# loicpinuela2.net
KiCad netlist of a schematic drawn in Altium Designer
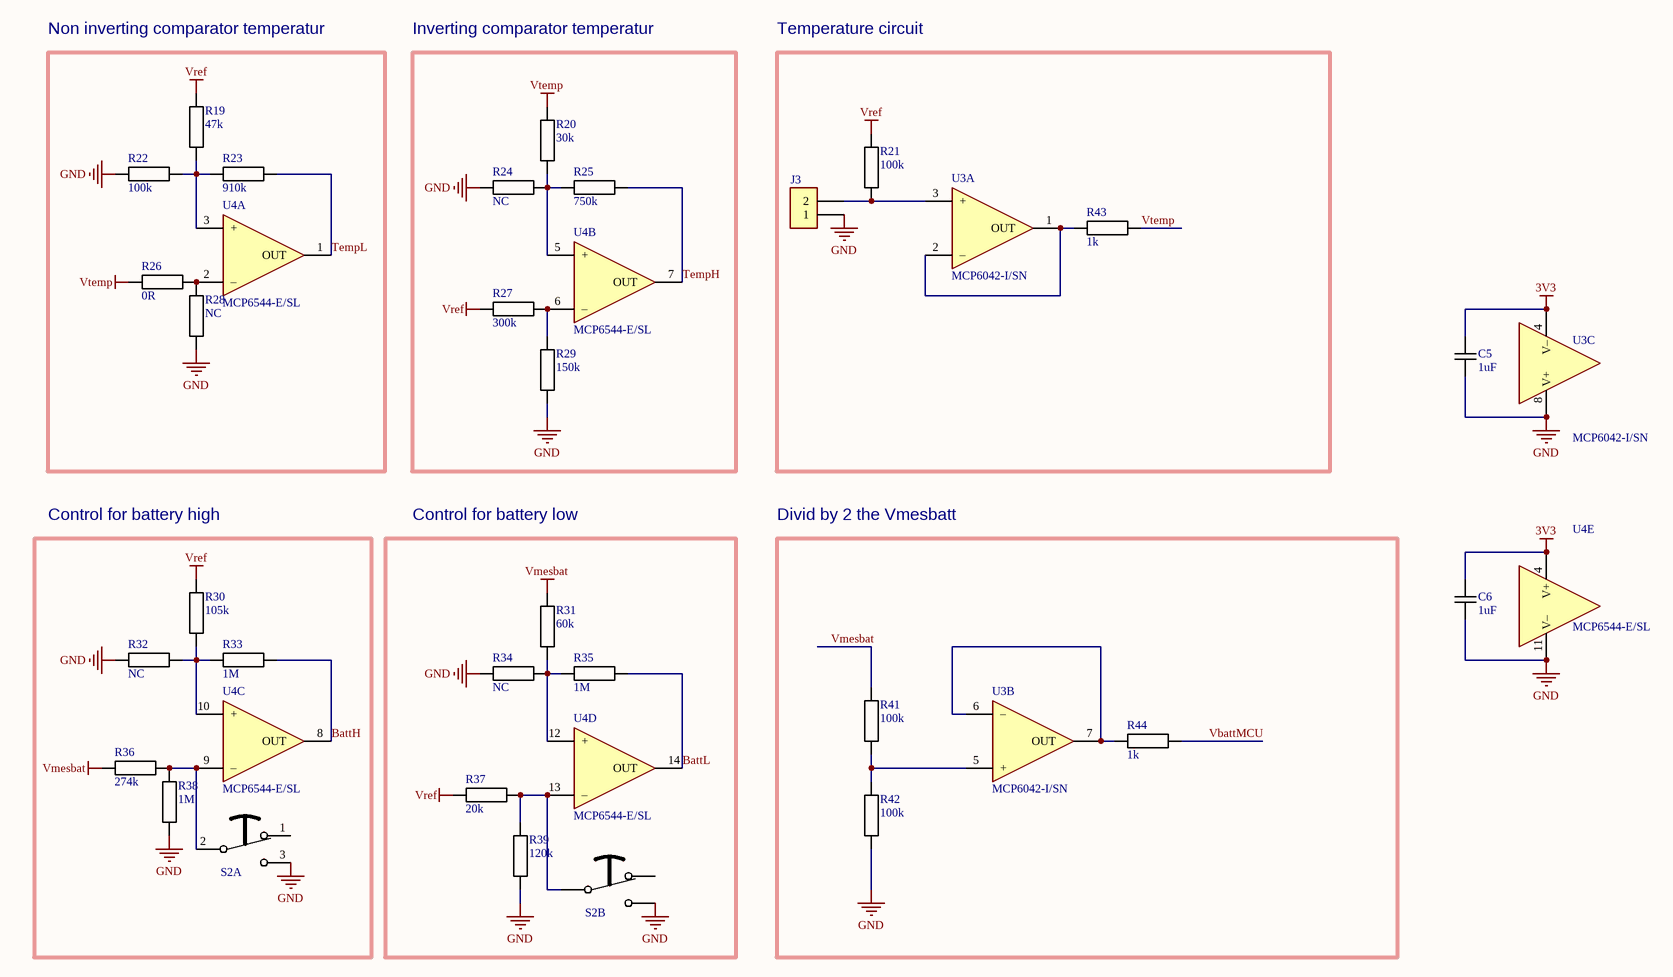
[diagram p0: loicpinuela2.SchDoc]

(export (version "E")
  (design (tool "Eeschema 10.0.6"))
  (components
    (comp (ref "C5")
      (value "1uF")
      (footprint "CAPACITOR 2012 REFLOW")
      (description "Capacitor")
      (libsource (lib "Capacitor") (part "Capacitor"))
    )
    (comp (ref "C6")
      (value "1uF")
      (footprint "CAPACITOR 2012 REFLOW")
      (description "Capacitor")
      (libsource (lib "Capacitor") (part "Capacitor"))
    )
    (comp (ref "J3")
      (value "~")
      (footprint "Socket1x2 P2.54")
      (description "Receptacle connector")
      (libsource (lib "PinHeader") (part "Socket1x2"))
    )
    (comp (ref "R19")
      (value "47k")
      (footprint "RESISTOR 2012 REFLOW")
      (description "Resistor")
      (fields (field (name "TOLERANCE") "1%"))
      (libsource (lib "Resistor") (part "Resistor"))
    )
    (comp (ref "R20")
      (value "30k")
      (footprint "RESISTOR 2012 REFLOW")
      (description "Resistor")
      (fields (field (name "TOLERANCE") "1%"))
      (libsource (lib "Resistor") (part "Resistor"))
    )
    (comp (ref "R21")
      (value "100k")
      (footprint "RESISTOR 2012 REFLOW")
      (description "Resistor")
      (fields (field (name "TOLERANCE") "1%"))
      (libsource (lib "Resistor") (part "Resistor"))
    )
    (comp (ref "R22")
      (value "100k")
      (footprint "RESISTOR 2012 REFLOW")
      (description "Resistor")
      (fields (field (name "TOLERANCE") "1%"))
      (libsource (lib "Resistor") (part "Resistor"))
    )
    (comp (ref "R23")
      (value "910k")
      (footprint "RESISTOR 2012 REFLOW")
      (description "Resistor")
      (fields (field (name "TOLERANCE") "1%"))
      (libsource (lib "Resistor") (part "Resistor"))
    )
    (comp (ref "R24")
      (value "NC")
      (footprint "RESISTOR 2012 REFLOW")
      (description "Resistor")
      (fields (field (name "TOLERANCE") "1%"))
      (libsource (lib "Resistor") (part "Resistor"))
    )
    (comp (ref "R25")
      (value "750k")
      (footprint "RESISTOR 2012 REFLOW")
      (description "Resistor")
      (fields (field (name "TOLERANCE") "1%"))
      (libsource (lib "Resistor") (part "Resistor"))
    )
    (comp (ref "R26")
      (value "0R")
      (footprint "RESISTOR 2012 REFLOW")
      (description "Resistor")
      (fields (field (name "TOLERANCE") "1%"))
      (libsource (lib "Resistor") (part "Resistor"))
    )
    (comp (ref "R27")
      (value "300k")
      (footprint "RESISTOR 2012 REFLOW")
      (description "Resistor")
      (fields (field (name "TOLERANCE") "1%"))
      (libsource (lib "Resistor") (part "Resistor"))
    )
    (comp (ref "R28")
      (value "NC")
      (footprint "RESISTOR 2012 REFLOW")
      (description "Resistor")
      (fields (field (name "TOLERANCE") "1%"))
      (libsource (lib "Resistor") (part "Resistor"))
    )
    (comp (ref "R29")
      (value "150k")
      (footprint "RESISTOR 2012 REFLOW")
      (description "Resistor")
      (fields (field (name "TOLERANCE") "1%"))
      (libsource (lib "Resistor") (part "Resistor"))
    )
    (comp (ref "R30")
      (value "105k")
      (footprint "RESISTOR 2012 REFLOW")
      (description "Resistor")
      (fields (field (name "TOLERANCE") "1%"))
      (libsource (lib "Resistor") (part "Resistor"))
    )
    (comp (ref "R31")
      (value "60k")
      (footprint "RESISTOR 2012 REFLOW")
      (description "Resistor")
      (fields (field (name "TOLERANCE") "1%"))
      (libsource (lib "Resistor") (part "Resistor"))
    )
    (comp (ref "R32")
      (value "NC")
      (footprint "RESISTOR 2012 REFLOW")
      (description "Resistor")
      (fields (field (name "TOLERANCE") "1%"))
      (libsource (lib "Resistor") (part "Resistor"))
    )
    (comp (ref "R33")
      (value "1M")
      (footprint "RESISTOR 2012 REFLOW")
      (description "Resistor")
      (fields (field (name "TOLERANCE") "1%"))
      (libsource (lib "Resistor") (part "Resistor"))
    )
    (comp (ref "R34")
      (value "NC")
      (footprint "RESISTOR 2012 REFLOW")
      (description "Resistor")
      (fields (field (name "TOLERANCE") "1%"))
      (libsource (lib "Resistor") (part "Resistor"))
    )
    (comp (ref "R35")
      (value "1M")
      (footprint "RESISTOR 2012 REFLOW")
      (description "Resistor")
      (fields (field (name "TOLERANCE") "1%"))
      (libsource (lib "Resistor") (part "Resistor"))
    )
    (comp (ref "R36")
      (value "274k")
      (footprint "RESISTOR 2012 REFLOW")
      (description "Resistor")
      (fields (field (name "TOLERANCE") "1%"))
      (libsource (lib "Resistor") (part "Resistor"))
    )
    (comp (ref "R37")
      (value "20k")
      (footprint "RESISTOR 2012 REFLOW")
      (description "Resistor")
      (fields (field (name "TOLERANCE") "1%"))
      (libsource (lib "Resistor") (part "Resistor"))
    )
    (comp (ref "R38")
      (value "1M")
      (footprint "RESISTOR 2012 REFLOW")
      (description "Resistor")
      (fields (field (name "TOLERANCE") "1%"))
      (libsource (lib "Resistor") (part "Resistor"))
    )
    (comp (ref "R39")
      (value "120k")
      (footprint "RESISTOR 2012 REFLOW")
      (description "Resistor")
      (fields (field (name "TOLERANCE") "1%"))
      (libsource (lib "Resistor") (part "Resistor"))
    )
    (comp (ref "R41")
      (value "100k")
      (footprint "RESISTOR 2012 REFLOW")
      (description "Resistor")
      (fields (field (name "TOLERANCE") "1%"))
      (libsource (lib "Resistor") (part "Resistor"))
    )
    (comp (ref "R42")
      (value "100k")
      (footprint "RESISTOR 2012 REFLOW")
      (description "Resistor")
      (fields (field (name "TOLERANCE") "1%"))
      (libsource (lib "Resistor") (part "Resistor"))
    )
    (comp (ref "R43")
      (value "1k")
      (footprint "RESISTOR 2012 REFLOW")
      (description "Resistor")
      (fields (field (name "TOLERANCE") "1%"))
      (libsource (lib "Resistor") (part "Resistor"))
    )
    (comp (ref "R44")
      (value "1k")
      (footprint "RESISTOR 2012 REFLOW")
      (description "Resistor")
      (fields (field (name "TOLERANCE") "1%"))
      (libsource (lib "Resistor") (part "Resistor"))
    )
    (comp (ref "S2")
      (value "*")
      (footprint "Push Button E-Switch TL2233")
      (description "Pushbutton, DPDT, SMD Switch")
      (libsource (lib "Button") (part "Push Button E-Switch TL2233"))
    )
    (comp (ref "U3")
      (value "MCP6042-I/SN")
      (footprint "SO8 P1.27 C4.0X5.0 H1.75")
      (description "Generic dual OPA 8 pins")
      (libsource (lib "Amplifier") (part "OPA DUAL"))
    )
    (comp (ref "U4")
      (value "MCP6544-E/SL")
      (footprint "SO14 P1.27 C4.0X8.8 H1.75")
      (description "Generic quad comparator 14 pins, Outpout PIN 1-7-18-14")
      (libsource (lib "Comparator") (part "COMPARATOR QUAD OUT PIN 1-7-8-14"))
    )
  )
  (nets
    (net (code "1") (name "/BattH") (class "Default")
      (node (ref "R33") (pin "2") (pinfunction "2_2") (pintype "passive"))
      (node (ref "U4") (pin "8") (pinfunction "OUT_8") (pintype "passive"))
    )
    (net (code "2") (name "/BattL") (class "Default")
      (node (ref "R35") (pin "2") (pinfunction "2_2") (pintype "passive"))
      (node (ref "U4") (pin "14") (pinfunction "OUT_14") (pintype "passive"))
    )
    (net (code "3") (name "/TempH") (class "Default")
      (node (ref "R25") (pin "2") (pinfunction "2_2") (pintype "passive"))
      (node (ref "U4") (pin "7") (pinfunction "OUT_7") (pintype "passive"))
    )
    (net (code "4") (name "/TempL") (class "Default")
      (node (ref "R23") (pin "2") (pinfunction "2_2") (pintype "passive"))
      (node (ref "U4") (pin "1") (pinfunction "OUT_1") (pintype "passive"))
    )
    (net (code "5") (name "/VbattMCU") (class "Default")
      (node (ref "R44") (pin "2") (pinfunction "2_2") (pintype "passive"))
    )
    (net (code "6") (name "3V3") (class "Default")
      (node (ref "C5") (pin "2") (pinfunction "2_2") (pintype "passive"))
      (node (ref "C6") (pin "2") (pinfunction "2_2") (pintype "passive"))
      (node (ref "U3") (pin "4") (pinfunction "V–_4") (pintype "passive"))
      (node (ref "U4") (pin "4") (pinfunction "V+_4") (pintype "passive"))
    )
    (net (code "7") (name "GND") (class "Default")
      (node (ref "C5") (pin "1") (pinfunction "1_1") (pintype "passive"))
      (node (ref "C6") (pin "1") (pinfunction "1_1") (pintype "passive"))
      (node (ref "J3") (pin "1") (pinfunction "1_1") (pintype "passive"))
      (node (ref "R22") (pin "1") (pinfunction "1_1") (pintype "passive"))
      (node (ref "R24") (pin "1") (pinfunction "1_1") (pintype "passive"))
      (node (ref "R28") (pin "1") (pinfunction "1_1") (pintype "passive"))
      (node (ref "R29") (pin "2") (pinfunction "2_2") (pintype "passive"))
      (node (ref "R32") (pin "1") (pinfunction "1_1") (pintype "passive"))
      (node (ref "R34") (pin "1") (pinfunction "1_1") (pintype "passive"))
      (node (ref "R38") (pin "1") (pinfunction "1_1") (pintype "passive"))
      (node (ref "R39") (pin "2") (pinfunction "2_2") (pintype "passive"))
      (node (ref "R42") (pin "1") (pinfunction "1_1") (pintype "passive"))
      (node (ref "S2") (pin "3") (pinfunction "NO1_3") (pintype "passive"))
      (node (ref "S2") (pin "4") (pinfunction "NO2_4") (pintype "passive"))
      (node (ref "U3") (pin "8") (pinfunction "V+_8") (pintype "passive"))
      (node (ref "U4") (pin "11") (pinfunction "V–_11") (pintype "passive"))
    )
    (net (code "8") (name "Net-(S2A-COM1)") (class "Default")
      (node (ref "R36") (pin "2") (pinfunction "2_2") (pintype "passive"))
      (node (ref "R38") (pin "2") (pinfunction "2_2") (pintype "passive"))
      (node (ref "S2") (pin "2") (pinfunction "COM1_2") (pintype "passive"))
      (node (ref "U4") (pin "9") (pinfunction "–_9") (pintype "passive"))
    )
    (net (code "9") (name "Net-(S2B-COM2)") (class "Default")
      (node (ref "R37") (pin "2") (pinfunction "2_2") (pintype "passive"))
      (node (ref "R39") (pin "1") (pinfunction "1_1") (pintype "passive"))
      (node (ref "S2") (pin "5") (pinfunction "COM2_5") (pintype "passive"))
      (node (ref "U4") (pin "13") (pinfunction "–_13") (pintype "passive"))
    )
    (net (code "10") (name "Net-(U3A-+)") (class "Default")
      (node (ref "J3") (pin "2") (pinfunction "2_2") (pintype "passive"))
      (node (ref "R21") (pin "1") (pinfunction "1_1") (pintype "passive"))
      (node (ref "U3") (pin "3") (pinfunction "+_3") (pintype "passive"))
    )
    (net (code "11") (name "Net-(U3A-OUT)") (class "Default")
      (node (ref "R43") (pin "1") (pinfunction "1_1") (pintype "passive"))
      (node (ref "U3") (pin "1") (pinfunction "OUT_1") (pintype "passive"))
      (node (ref "U3") (pin "2") (pinfunction "–_2") (pintype "passive"))
    )
    (net (code "12") (name "Net-(U3B-+)") (class "Default")
      (node (ref "R41") (pin "1") (pinfunction "1_1") (pintype "passive"))
      (node (ref "R42") (pin "2") (pinfunction "2_2") (pintype "passive"))
      (node (ref "U3") (pin "5") (pinfunction "+_5") (pintype "passive"))
    )
    (net (code "13") (name "Net-(U3B-OUT)") (class "Default")
      (node (ref "R44") (pin "1") (pinfunction "1_1") (pintype "passive"))
      (node (ref "U3") (pin "6") (pinfunction "–_6") (pintype "passive"))
      (node (ref "U3") (pin "7") (pinfunction "OUT_7") (pintype "passive"))
    )
    (net (code "14") (name "Net-(U4A-+)") (class "Default")
      (node (ref "R19") (pin "1") (pinfunction "1_1") (pintype "passive"))
      (node (ref "R22") (pin "2") (pinfunction "2_2") (pintype "passive"))
      (node (ref "R23") (pin "1") (pinfunction "1_1") (pintype "passive"))
      (node (ref "U4") (pin "3") (pinfunction "+_3") (pintype "passive"))
    )
    (net (code "15") (name "Net-(U4A-–)") (class "Default")
      (node (ref "R26") (pin "2") (pinfunction "2_2") (pintype "passive"))
      (node (ref "R28") (pin "2") (pinfunction "2_2") (pintype "passive"))
      (node (ref "U4") (pin "2") (pinfunction "–_2") (pintype "passive"))
    )
    (net (code "16") (name "Net-(U4B-+)") (class "Default")
      (node (ref "R20") (pin "1") (pinfunction "1_1") (pintype "passive"))
      (node (ref "R24") (pin "2") (pinfunction "2_2") (pintype "passive"))
      (node (ref "R25") (pin "1") (pinfunction "1_1") (pintype "passive"))
      (node (ref "U4") (pin "5") (pinfunction "+_5") (pintype "passive"))
    )
    (net (code "17") (name "Net-(U4B-–)") (class "Default")
      (node (ref "R27") (pin "2") (pinfunction "2_2") (pintype "passive"))
      (node (ref "R29") (pin "1") (pinfunction "1_1") (pintype "passive"))
      (node (ref "U4") (pin "6") (pinfunction "–_6") (pintype "passive"))
    )
    (net (code "18") (name "Net-(U4C-+)") (class "Default")
      (node (ref "R30") (pin "1") (pinfunction "1_1") (pintype "passive"))
      (node (ref "R32") (pin "2") (pinfunction "2_2") (pintype "passive"))
      (node (ref "R33") (pin "1") (pinfunction "1_1") (pintype "passive"))
      (node (ref "U4") (pin "10") (pinfunction "+_10") (pintype "passive"))
    )
    (net (code "19") (name "Net-(U4D-+)") (class "Default")
      (node (ref "R31") (pin "1") (pinfunction "1_1") (pintype "passive"))
      (node (ref "R34") (pin "2") (pinfunction "2_2") (pintype "passive"))
      (node (ref "R35") (pin "1") (pinfunction "1_1") (pintype "passive"))
      (node (ref "U4") (pin "12") (pinfunction "+_12") (pintype "passive"))
    )
    (net (code "20") (name "Vmesbat") (class "Default")
      (node (ref "R31") (pin "2") (pinfunction "2_2") (pintype "passive"))
      (node (ref "R36") (pin "1") (pinfunction "1_1") (pintype "passive"))
      (node (ref "R41") (pin "2") (pinfunction "2_2") (pintype "passive"))
    )
    (net (code "21") (name "Vref") (class "Default")
      (node (ref "R19") (pin "2") (pinfunction "2_2") (pintype "passive"))
      (node (ref "R21") (pin "2") (pinfunction "2_2") (pintype "passive"))
      (node (ref "R27") (pin "1") (pinfunction "1_1") (pintype "passive"))
      (node (ref "R30") (pin "2") (pinfunction "2_2") (pintype "passive"))
      (node (ref "R37") (pin "1") (pinfunction "1_1") (pintype "passive"))
    )
    (net (code "22") (name "Vtemp") (class "Default")
      (node (ref "R20") (pin "2") (pinfunction "2_2") (pintype "passive"))
      (node (ref "R26") (pin "1") (pinfunction "1_1") (pintype "passive"))
      (node (ref "R43") (pin "2") (pinfunction "2_2") (pintype "passive"))
    )
    (net (code "23") (name "unconnected-(S2A-NC1-Pad1)") (class "Default")
      (node (ref "S2") (pin "1") (pinfunction "NC1_1") (pintype "passive"))
    )
    (net (code "24") (name "unconnected-(S2B-NC2-Pad6)") (class "Default")
      (node (ref "S2") (pin "6") (pinfunction "NC2_6") (pintype "passive"))
    )
  )
)
